# MotorPID.net
KiCad netlist of a schematic drawn in Altium Designer
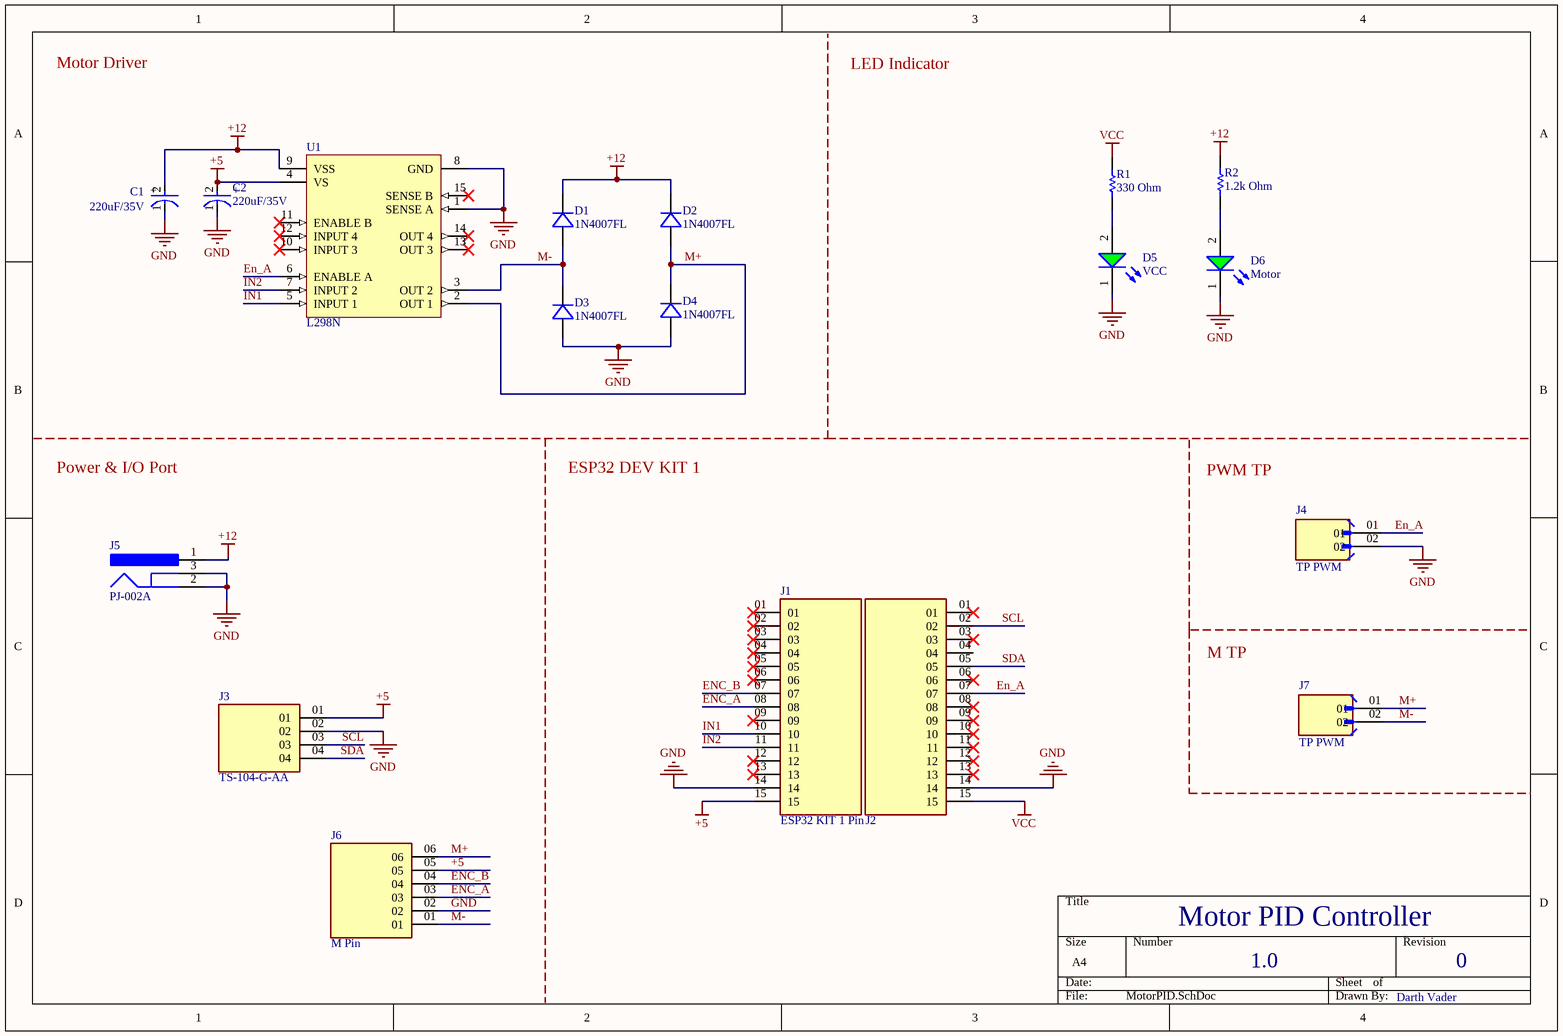
[diagram p0: MotorPID.SchDoc]

(export (version "E")
  (design (tool "Eeschema 10.0.6"))
  (components
    (comp (ref "C1")
      (value "220uF/35V")
      (footprint "FP-FKF-MFG")
      (description "CAP ALUM 220UF 20% 35V SMD")
      (fields (field (name "VOLTAGE") "35V") (field (name "TOLERANCE") "20%"))
      (libsource (lib "Altium Content Vault") (part "a00bbbee19879c290e62620ae7e47b1"))
    )
    (comp (ref "C2")
      (value "220uF/35V")
      (footprint "FP-FKF-MFG")
      (description "CAP ALUM 220UF 20% 35V SMD")
      (fields (field (name "VOLTAGE") "35V") (field (name "TOLERANCE") "20%"))
      (libsource (lib "Altium Content Vault") (part "a00bbbee19879c290e62620ae7e47b1"))
    )
    (comp (ref "D1")
      (value "1N4007FL")
      (footprint "CR_SOD-123FL_SME-L")
      (description "No Description Available")
      (libsource (lib "MotorPID") (part "1N4007FL"))
    )
    (comp (ref "D2")
      (value "1N4007FL")
      (footprint "CR_SOD-123FL_SME-L")
      (description "No Description Available")
      (libsource (lib "MotorPID") (part "1N4007FL"))
    )
    (comp (ref "D3")
      (value "1N4007FL")
      (footprint "CR_SOD-123FL_SME-L")
      (description "No Description Available")
      (libsource (lib "MotorPID") (part "1N4007FL"))
    )
    (comp (ref "D4")
      (value "1N4007FL")
      (footprint "CR_SOD-123FL_SME-L")
      (description "No Description Available")
      (libsource (lib "MotorPID") (part "1N4007FL"))
    )
    (comp (ref "D5")
      (value "VCC")
      (footprint "WL-SMCW_1206_150120xx75000")
      (description "WL-SMCW SMT Mono-Color Chip LED Waterclear 1206")
      (libsource (lib "Altium Content Vault") (part "LED_Green_2A-1K"))
    )
    (comp (ref "D6")
      (value "Motor")
      (footprint "WL-SMCW_1206_150120xx75000")
      (description "WL-SMCW SMT Mono-Color Chip LED Waterclear 1206")
      (libsource (lib "Altium Content Vault") (part "LED_Green_2A-1K"))
    )
    (comp (ref "J1")
      (value "ESP32 KIT 1 Pin")
      (footprint "SAMTEC_TS-115-T-A")
      (fields (field (name "MF") "Samtec Inc.") (field (name "MP") "TS-115-T-A"))
      (libsource (lib "MotorPID") (part "TS-115-T-A"))
    )
    (comp (ref "J2")
      (value "TS-115-T-A")
      (footprint "SAMTEC_TS-115-T-A")
      (fields (field (name "MF") "Samtec Inc."))
      (libsource (lib "") (part "TS-115-T-A_1"))
    )
    (comp (ref "J3")
      (value "TS-104-G-AA")
      (footprint "MotorPID:SAMTEC_TS-104-G-AA")
      (fields (field (name "MF") "Samtec Inc."))
      (libsource (lib "MotorPID") (part "TS-104-G-AA"))
    )
    (comp (ref "J4")
      (value "TP PWM")
      (footprint "SULLINS_GRPB021VWVN-RC")
      (fields (field (name "MP") "GRPB021VWVN-RC"))
      (libsource (lib "MotorPID") (part "GRPB021VWVN-RC"))
    )
    (comp (ref "J5")
      (value "PJ-002A")
      (footprint "CUI-PJ-002A_V")
      (fields (field (name "MANUFACTURER") "CUIInc."))
      (libsource (lib "Altium Content Vault") (part "JACK-2CD3-RN_B"))
    )
    (comp (ref "J6")
      (value "M Pin")
      (footprint "SAMTEC_TS-106-G-AA")
      (description "Conn Unshrouded Header HDR 6 POS 2.54mm Solder ST Thru-Hole Tube")
      (fields (field (name "MF") "Samtec") (field (name "MP") "TS-106-G-AA"))
      (libsource (lib "MotorPID") (part "TS-106-G-AA"))
    )
    (comp (ref "J7")
      (value "TP PWM")
      (footprint "SULLINS_GRPB021VWVN-RC")
      (fields (field (name "MP") "GRPB021VWVN-RC"))
      (libsource (lib "MotorPID") (part "GRPB021VWVN-RC"))
    )
    (comp (ref "R1")
      (value "330 Ohm")
      (footprint "RESC3216X70X50LL05T20")
      (fields (field (name "MANUFACTURER") "Panasonic") (field (name "PART NUMBER") "ERJ-8ENF1001V"))
      (libsource (lib "Altium Content Vault") (part "RES"))
    )
    (comp (ref "R2")
      (value "1.2k Ohm")
      (footprint "RESC3216X70X50LL05T20")
      (fields (field (name "MANUFACTURER") "Panasonic") (field (name "PART NUMBER") "ERJ-8ENF1001V"))
      (libsource (lib "Altium Content Vault") (part "RES"))
    )
    (comp (ref "U1")
      (value "L298N")
      (footprint "STM-FM-15")
      (description "Dual Full-Bridge Driver, 4.8 to 46 V, -40 to 150 degC, 15-Pin FM (MW 15L), RoHS, Tube")
      (fields (field (name "MANUFACTURER") "STMicroelectronics") (field (name "PARTNUMBER") "L298"))
      (libsource (lib "Altium Content Vault") (part "STM-L298-15"))
    )
  )
  (nets
    (net (code "1") (name "+5") (class "Default")
      (node (ref "C2") (pin "2") (pinfunction "A_2") (pintype "passive"))
      (node (ref "J1") (pin "15") (pinfunction "15_15") (pintype "passive"))
      (node (ref "J3") (pin "01") (pinfunction "01_01") (pintype "passive"))
      (node (ref "J6") (pin "05") (pinfunction "05_05") (pintype "passive"))
      (node (ref "U1") (pin "4") (pinfunction "VS_4") (pintype "power_in"))
    )
    (net (code "2") (name "+12") (class "Default")
      (node (ref "C1") (pin "2") (pinfunction "A_2") (pintype "passive"))
      (node (ref "D1") (pin "1") (pinfunction "CATHODE_1") (pintype "passive"))
      (node (ref "D2") (pin "1") (pinfunction "CATHODE_1") (pintype "passive"))
      (node (ref "J5") (pin "1") (pinfunction "1_1") (pintype "passive"))
      (node (ref "R2") (pin "2") (pinfunction "2_2") (pintype "passive"))
      (node (ref "U1") (pin "9") (pinfunction "VSS_9") (pintype "power_in"))
    )
    (net (code "3") (name "/ENC_A") (class "Default")
      (node (ref "J1") (pin "08") (pinfunction "08_08") (pintype "passive"))
      (node (ref "J6") (pin "03") (pinfunction "03_03") (pintype "passive"))
    )
    (net (code "4") (name "/ENC_B") (class "Default")
      (node (ref "J1") (pin "07") (pinfunction "07_07") (pintype "passive"))
      (node (ref "J6") (pin "04") (pinfunction "04_04") (pintype "passive"))
    )
    (net (code "5") (name "/En_A") (class "Default")
      (node (ref "J2") (pin "07") (pinfunction "07_07") (pintype "passive"))
      (node (ref "J4") (pin "01") (pinfunction "01_01") (pintype "passive"))
      (node (ref "U1") (pin "6") (pinfunction "ENABLE_A_6") (pintype "input"))
    )
    (net (code "6") (name "/IN1") (class "Default")
      (node (ref "J1") (pin "10") (pinfunction "10_10") (pintype "passive"))
      (node (ref "U1") (pin "5") (pinfunction "INPUT_1_5") (pintype "input"))
    )
    (net (code "7") (name "/IN2") (class "Default")
      (node (ref "J1") (pin "11") (pinfunction "11_11") (pintype "passive"))
      (node (ref "U1") (pin "7") (pinfunction "INPUT_2_7") (pintype "input"))
    )
    (net (code "8") (name "/M+") (class "Default")
      (node (ref "D2") (pin "2") (pinfunction "ANODE_2") (pintype "passive"))
      (node (ref "D4") (pin "1") (pinfunction "CATHODE_1") (pintype "passive"))
      (node (ref "J6") (pin "06") (pinfunction "06_06") (pintype "passive"))
      (node (ref "J7") (pin "01") (pinfunction "01_01") (pintype "passive"))
      (node (ref "U1") (pin "2") (pinfunction "OUT_1_2") (pintype "output"))
    )
    (net (code "9") (name "/M-") (class "Default")
      (node (ref "D1") (pin "2") (pinfunction "ANODE_2") (pintype "passive"))
      (node (ref "D3") (pin "1") (pinfunction "CATHODE_1") (pintype "passive"))
      (node (ref "J6") (pin "01") (pinfunction "01_01") (pintype "passive"))
      (node (ref "J7") (pin "02") (pinfunction "02_02") (pintype "passive"))
      (node (ref "U1") (pin "3") (pinfunction "OUT_2_3") (pintype "output"))
    )
    (net (code "10") (name "/SCL") (class "Default")
      (node (ref "J2") (pin "02") (pinfunction "02_02") (pintype "passive"))
      (node (ref "J3") (pin "03") (pinfunction "03_03") (pintype "passive"))
    )
    (net (code "11") (name "/SDA") (class "Default")
      (node (ref "J2") (pin "05") (pinfunction "05_05") (pintype "passive"))
      (node (ref "J3") (pin "04") (pinfunction "04_04") (pintype "passive"))
    )
    (net (code "12") (name "GND") (class "Default")
      (node (ref "C1") (pin "1") (pinfunction "C_1") (pintype "passive"))
      (node (ref "C2") (pin "1") (pinfunction "C_1") (pintype "passive"))
      (node (ref "D3") (pin "2") (pinfunction "ANODE_2") (pintype "passive"))
      (node (ref "D4") (pin "2") (pinfunction "ANODE_2") (pintype "passive"))
      (node (ref "D5") (pin "1") (pinfunction "K_1") (pintype "passive"))
      (node (ref "D6") (pin "1") (pinfunction "K_1") (pintype "passive"))
      (node (ref "J1") (pin "14") (pinfunction "14_14") (pintype "passive"))
      (node (ref "J2") (pin "14") (pinfunction "14_14") (pintype "passive"))
      (node (ref "J3") (pin "02") (pinfunction "02_02") (pintype "passive"))
      (node (ref "J4") (pin "02") (pinfunction "02_02") (pintype "passive"))
      (node (ref "J5") (pin "2") (pinfunction "2_2") (pintype "passive"))
      (node (ref "J5") (pin "3") (pinfunction "3_3") (pintype "passive"))
      (node (ref "J6") (pin "02") (pinfunction "02_02") (pintype "passive"))
      (node (ref "U1") (pin "1") (pinfunction "SENSE_A_1") (pintype "input"))
      (node (ref "U1") (pin "8") (pinfunction "GND_8") (pintype "power_in"))
    )
    (net (code "13") (name "Net-(D5-A)") (class "Default")
      (node (ref "D5") (pin "2") (pinfunction "A_2") (pintype "passive"))
      (node (ref "R1") (pin "1") (pinfunction "1_1") (pintype "passive"))
    )
    (net (code "14") (name "Net-(D6-A)") (class "Default")
      (node (ref "D6") (pin "2") (pinfunction "A_2") (pintype "passive"))
      (node (ref "R2") (pin "1") (pinfunction "1_1") (pintype "passive"))
    )
    (net (code "15") (name "VCC") (class "Default")
      (node (ref "J2") (pin "15") (pinfunction "15_15") (pintype "passive"))
      (node (ref "R1") (pin "2") (pinfunction "2_2") (pintype "passive"))
    )
    (net (code "16") (name "unconnected-(J1-Pad01)") (class "Default")
      (node (ref "J1") (pin "01") (pinfunction "01_01") (pintype "passive+no_connect"))
    )
    (net (code "17") (name "unconnected-(J1-Pad02)") (class "Default")
      (node (ref "J1") (pin "02") (pinfunction "02_02") (pintype "passive+no_connect"))
    )
    (net (code "18") (name "unconnected-(J1-Pad03)") (class "Default")
      (node (ref "J1") (pin "03") (pinfunction "03_03") (pintype "passive+no_connect"))
    )
    (net (code "19") (name "unconnected-(J1-Pad04)") (class "Default")
      (node (ref "J1") (pin "04") (pinfunction "04_04") (pintype "passive+no_connect"))
    )
    (net (code "20") (name "unconnected-(J1-Pad05)") (class "Default")
      (node (ref "J1") (pin "05") (pinfunction "05_05") (pintype "passive+no_connect"))
    )
    (net (code "21") (name "unconnected-(J1-Pad06)") (class "Default")
      (node (ref "J1") (pin "06") (pinfunction "06_06") (pintype "passive+no_connect"))
    )
    (net (code "22") (name "unconnected-(J1-Pad09)") (class "Default")
      (node (ref "J1") (pin "09") (pinfunction "09_09") (pintype "passive+no_connect"))
    )
    (net (code "23") (name "unconnected-(J1-Pad12)") (class "Default")
      (node (ref "J1") (pin "12") (pinfunction "12_12") (pintype "passive+no_connect"))
    )
    (net (code "24") (name "unconnected-(J1-Pad13)") (class "Default")
      (node (ref "J1") (pin "13") (pinfunction "13_13") (pintype "passive+no_connect"))
    )
    (net (code "25") (name "unconnected-(J2-Pad01)") (class "Default")
      (node (ref "J2") (pin "01") (pinfunction "01_01") (pintype "passive+no_connect"))
    )
    (net (code "26") (name "unconnected-(J2-Pad03)") (class "Default")
      (node (ref "J2") (pin "03") (pinfunction "03_03") (pintype "passive+no_connect"))
    )
    (net (code "27") (name "unconnected-(J2-Pad04)") (class "Default")
      (node (ref "J2") (pin "04") (pinfunction "04_04") (pintype "passive"))
    )
    (net (code "28") (name "unconnected-(J2-Pad06)") (class "Default")
      (node (ref "J2") (pin "06") (pinfunction "06_06") (pintype "passive+no_connect"))
    )
    (net (code "29") (name "unconnected-(J2-Pad08)") (class "Default")
      (node (ref "J2") (pin "08") (pinfunction "08_08") (pintype "passive+no_connect"))
    )
    (net (code "30") (name "unconnected-(J2-Pad09)") (class "Default")
      (node (ref "J2") (pin "09") (pinfunction "09_09") (pintype "passive+no_connect"))
    )
    (net (code "31") (name "unconnected-(J2-Pad10)") (class "Default")
      (node (ref "J2") (pin "10") (pinfunction "10_10") (pintype "passive+no_connect"))
    )
    (net (code "32") (name "unconnected-(J2-Pad11)") (class "Default")
      (node (ref "J2") (pin "11") (pinfunction "11_11") (pintype "passive+no_connect"))
    )
    (net (code "33") (name "unconnected-(J2-Pad12)") (class "Default")
      (node (ref "J2") (pin "12") (pinfunction "12_12") (pintype "passive+no_connect"))
    )
    (net (code "34") (name "unconnected-(J2-Pad13)") (class "Default")
      (node (ref "J2") (pin "13") (pinfunction "13_13") (pintype "passive+no_connect"))
    )
    (net (code "35") (name "unconnected-(U1-ENABLE_B-Pad11)") (class "Default")
      (node (ref "U1") (pin "11") (pinfunction "ENABLE_B_11") (pintype "input+no_connect"))
    )
    (net (code "36") (name "unconnected-(U1-INPUT_3-Pad10)") (class "Default")
      (node (ref "U1") (pin "10") (pinfunction "INPUT_3_10") (pintype "input+no_connect"))
    )
    (net (code "37") (name "unconnected-(U1-INPUT_4-Pad12)") (class "Default")
      (node (ref "U1") (pin "12") (pinfunction "INPUT_4_12") (pintype "input+no_connect"))
    )
    (net (code "38") (name "unconnected-(U1-OUT_3-Pad13)") (class "Default")
      (node (ref "U1") (pin "13") (pinfunction "OUT_3_13") (pintype "output+no_connect"))
    )
    (net (code "39") (name "unconnected-(U1-OUT_4-Pad14)") (class "Default")
      (node (ref "U1") (pin "14") (pinfunction "OUT_4_14") (pintype "output+no_connect"))
    )
    (net (code "40") (name "unconnected-(U1-SENSE_B-Pad15)") (class "Default")
      (node (ref "U1") (pin "15") (pinfunction "SENSE_B_15") (pintype "input+no_connect"))
    )
  )
)
